# power_board.net
KiCad netlist of a schematic drawn in EAGLE
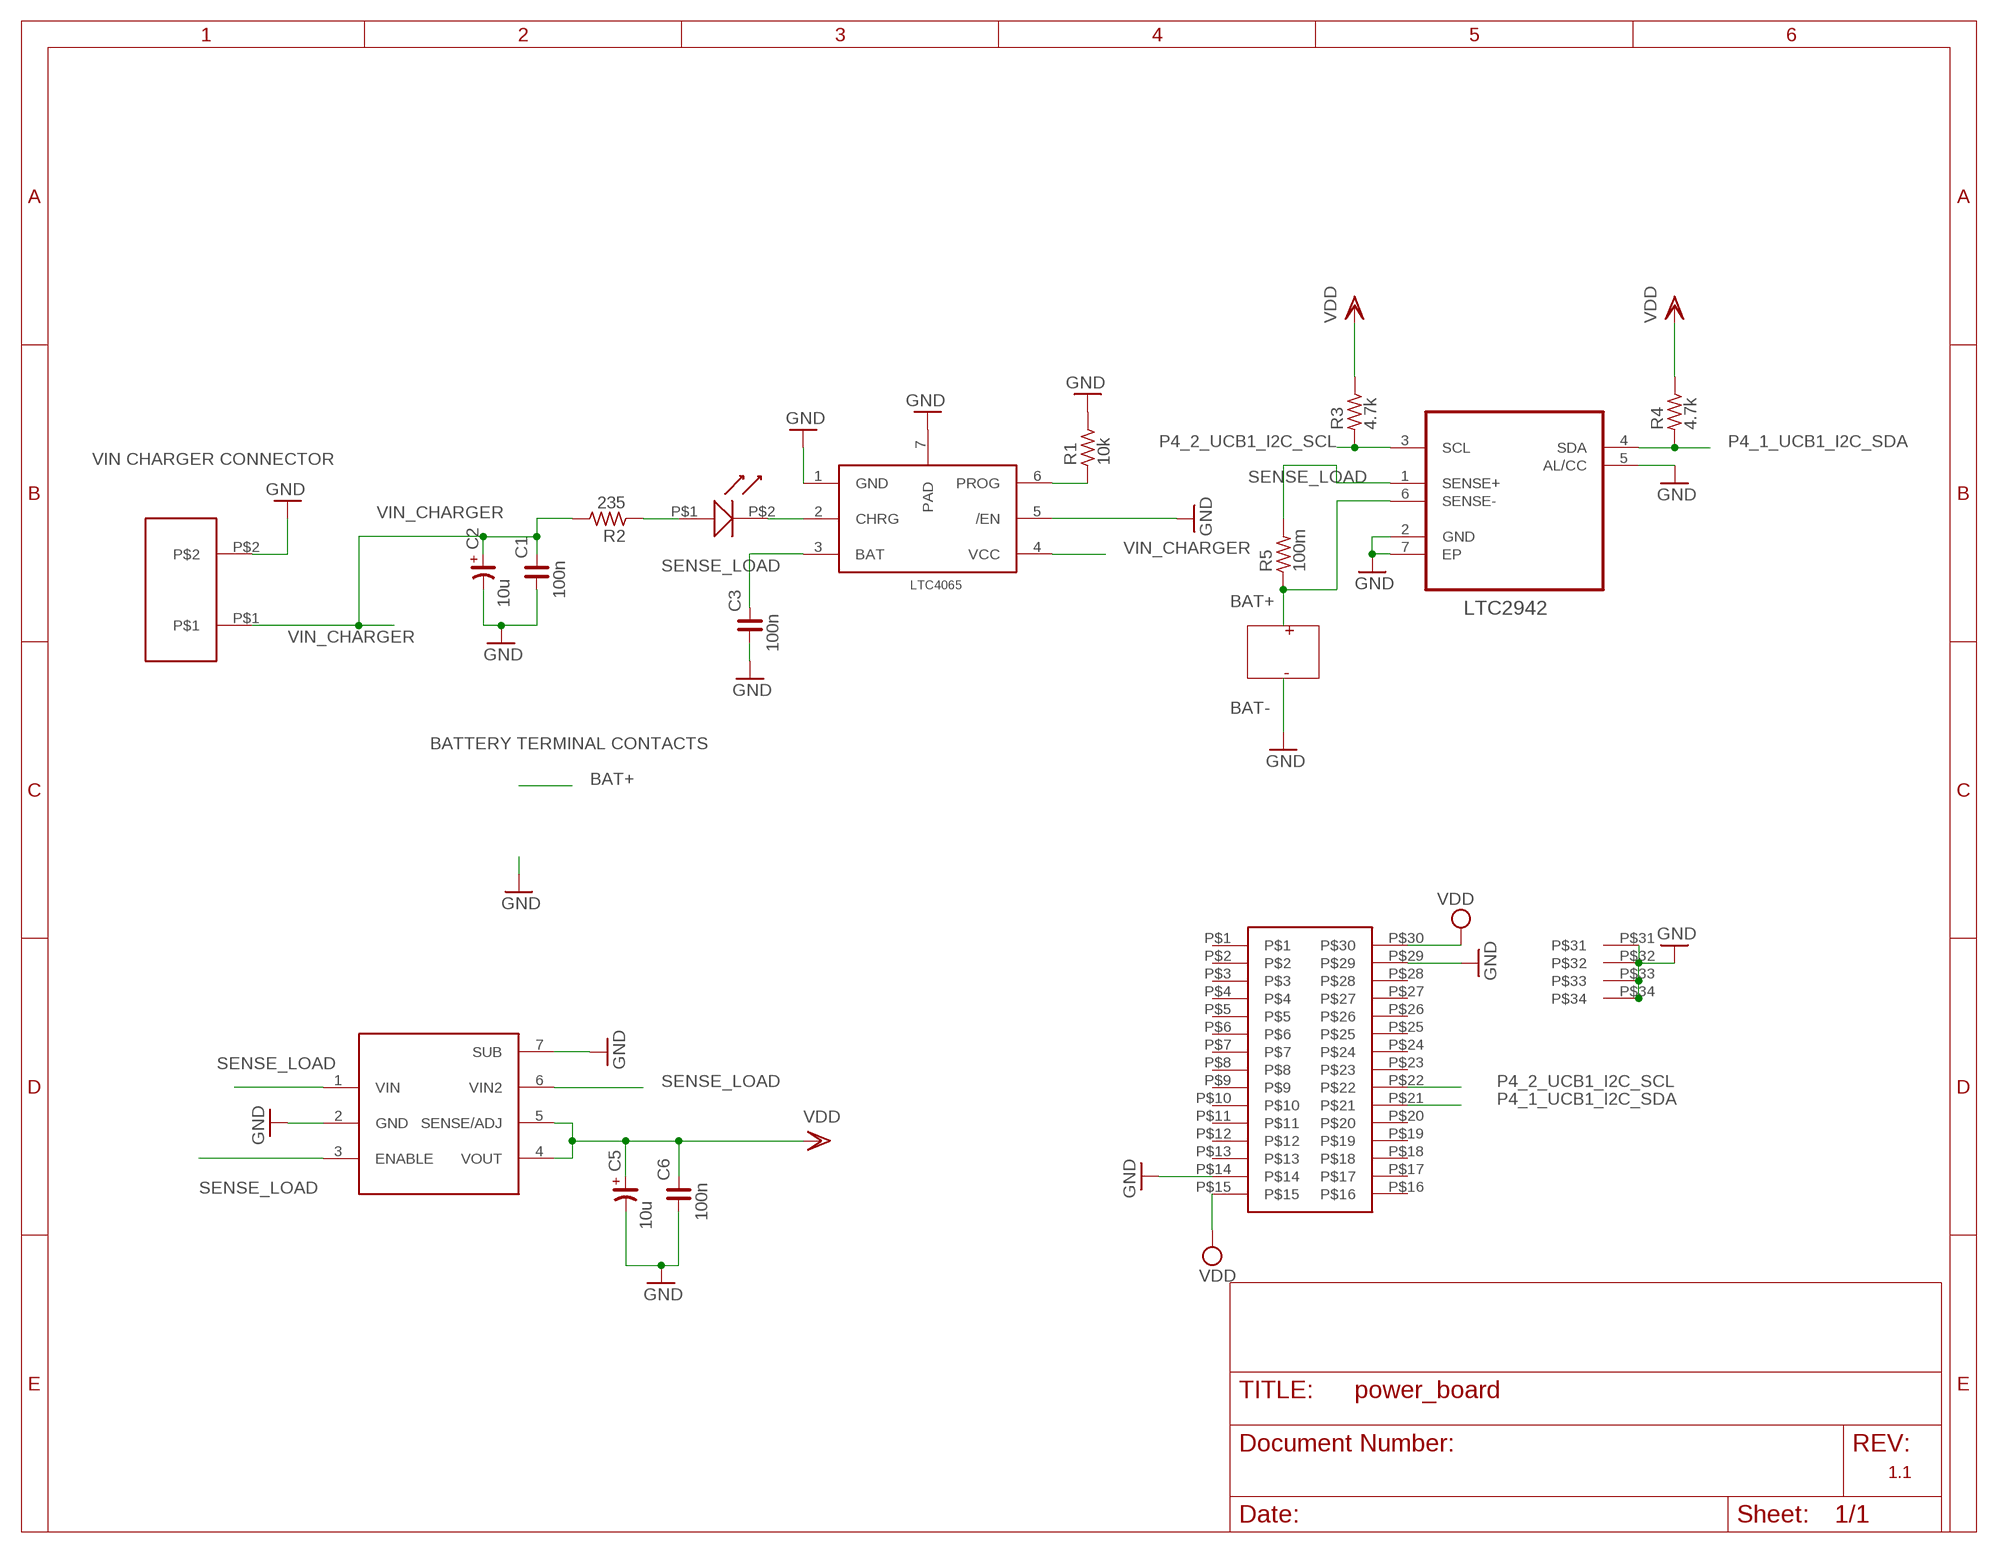
[diagram p0: schematic, sheet 1]

(export (version "E")
  (design (tool "Eeschema 10.0.6"))
  (components
    (comp (ref "C1")
      (value "100n")
      (footprint "eagle-import:C0402")
      (libsource (lib "eagle-import") (part "C_0402"))
    )
    (comp (ref "C2")
      (value "10u")
      (footprint "eagle-import:C0402")
      (libsource (lib "eagle-import") (part "CP_"))
    )
    (comp (ref "C3")
      (value "100n")
      (footprint "eagle-import:C0402")
      (libsource (lib "eagle-import") (part "C_0402"))
    )
    (comp (ref "C5")
      (value "10u")
      (footprint "eagle-import:C0402")
      (libsource (lib "eagle-import") (part "CP_"))
    )
    (comp (ref "C6")
      (value "100n")
      (footprint "eagle-import:C0402")
      (libsource (lib "eagle-import") (part "C_0402"))
    )
    (comp (ref "R1")
      (value "10k")
      (footprint "eagle-import:R0402")
      (libsource (lib "eagle-import") (part "R_0402"))
    )
    (comp (ref "R2")
      (value "235")
      (footprint "eagle-import:R0402")
      (libsource (lib "eagle-import") (part "R_0402"))
    )
    (comp (ref "R3")
      (value "4.7k")
      (footprint "eagle-import:R0402")
      (libsource (lib "eagle-import") (part "R_0402"))
    )
    (comp (ref "R4")
      (value "4.7k")
      (footprint "eagle-import:R0402")
      (libsource (lib "eagle-import") (part "R_0402"))
    )
    (comp (ref "R5")
      (value "100m")
      (footprint "eagle-import:R0402")
      (libsource (lib "eagle-import") (part "R_0402"))
    )
    (comp (ref "U$1")
      (value "LTC4065")
      (footprint "eagle-import:LTC4065")
      (libsource (lib "eagle-import") (part "LTC4065"))
    )
    (comp (ref "U$2")
      (value "LED0402")
      (footprint "eagle-import:LED_0402")
      (libsource (lib "eagle-import") (part "LED0402"))
    )
    (comp (ref "U$3")
      (value "55909-0374_PLUG")
      (footprint "eagle-import:55909-0374_PLUG")
      (libsource (lib "eagle-import") (part "55909-0374_PLUG"))
    )
    (comp (ref "U$4")
      (value "NCP606")
      (footprint "eagle-import:NCP606")
      (libsource (lib "eagle-import") (part "NCP606"))
    )
    (comp (ref "U$5")
      (value "ASR_2_REC")
      (footprint "eagle-import:ASR_2_CONN")
      (libsource (lib "eagle-import") (part "ASR_2_REC"))
    )
    (comp (ref "U1")
      (value "LTC2942CDCBTRMPBF")
      (footprint "eagle-import:DFN200X300X80-7N")
      (fields (field (name "MPN") "LTC2942CDCB#TRMPBF"))
      (libsource (lib "eagle-import") (part "LTC2942CDCBTRMPBF"))
    )
  )
  (nets
    (net (code "1") (name "/BAT+") (class "Default")
      (node (ref "R5") (pin "1") (pinfunction "1_1") (pintype "passive"))
      (node (ref "U1") (pin "6") (pinfunction "SENSE-_6") (pintype "input"))
    )
    (net (code "2") (name "/P4_1_UCB1_I2C_SDA") (class "Default")
      (node (ref "R4") (pin "1") (pinfunction "1_1") (pintype "passive"))
      (node (ref "U$3") (pin "P$21") (pinfunction "P$21_P$21") (pintype "bidirectional"))
      (node (ref "U1") (pin "4") (pinfunction "SDA_4") (pintype "bidirectional"))
    )
    (net (code "3") (name "/P4_2_UCB1_I2C_SCL") (class "Default")
      (node (ref "R3") (pin "1") (pinfunction "1_1") (pintype "passive"))
      (node (ref "U$3") (pin "P$22") (pinfunction "P$22_P$22") (pintype "bidirectional"))
      (node (ref "U1") (pin "3") (pinfunction "SCL_3") (pintype "input"))
    )
    (net (code "4") (name "/SENSE_LOAD") (class "Default")
      (node (ref "C3") (pin "2") (pinfunction "2_2") (pintype "passive"))
      (node (ref "R5") (pin "2") (pinfunction "2_2") (pintype "passive"))
      (node (ref "U$1") (pin "3") (pinfunction "BAT_3") (pintype "bidirectional"))
      (node (ref "U$4") (pin "1") (pinfunction "VIN_1") (pintype "bidirectional"))
      (node (ref "U$4") (pin "3") (pinfunction "ENABLE_3") (pintype "bidirectional"))
      (node (ref "U$4") (pin "6") (pinfunction "VIN2_6") (pintype "bidirectional"))
      (node (ref "U1") (pin "1") (pinfunction "SENSE+_1") (pintype "input"))
    )
    (net (code "5") (name "/VIN_CHARGER") (class "Default")
      (node (ref "C1") (pin "2") (pinfunction "2_2") (pintype "passive"))
      (node (ref "C2") (pin "1") (pinfunction "+_1") (pintype "passive"))
      (node (ref "R2") (pin "2") (pinfunction "2_2") (pintype "passive"))
      (node (ref "U$1") (pin "4") (pinfunction "VCC_4") (pintype "bidirectional"))
      (node (ref "U$5") (pin "P$1") (pinfunction "P$1_P$1") (pintype "bidirectional"))
    )
    (net (code "6") (name "GND") (class "Default")
      (node (ref "C1") (pin "1") (pinfunction "1_1") (pintype "passive"))
      (node (ref "C2") (pin "2") (pinfunction "-_2") (pintype "passive"))
      (node (ref "C3") (pin "1") (pinfunction "1_1") (pintype "passive"))
      (node (ref "C5") (pin "2") (pinfunction "-_2") (pintype "passive"))
      (node (ref "C6") (pin "1") (pinfunction "1_1") (pintype "passive"))
      (node (ref "R1") (pin "2") (pinfunction "2_2") (pintype "passive"))
      (node (ref "U$1") (pin "1") (pinfunction "GND_1") (pintype "bidirectional"))
      (node (ref "U$1") (pin "5") (pinfunction "/EN_5") (pintype "bidirectional"))
      (node (ref "U$1") (pin "7") (pinfunction "PAD_7") (pintype "bidirectional"))
      (node (ref "U$3") (pin "P$14") (pinfunction "P$14_P$14") (pintype "bidirectional"))
      (node (ref "U$3") (pin "P$29") (pinfunction "P$29_P$29") (pintype "bidirectional"))
      (node (ref "U$3") (pin "P$31") (pinfunction "P$31_P$31") (pintype "bidirectional"))
      (node (ref "U$3") (pin "P$32") (pinfunction "P$32_P$32") (pintype "bidirectional"))
      (node (ref "U$3") (pin "P$33") (pinfunction "P$33_P$33") (pintype "bidirectional"))
      (node (ref "U$3") (pin "P$34") (pinfunction "P$34_P$34") (pintype "bidirectional"))
      (node (ref "U$4") (pin "2") (pinfunction "GND_2") (pintype "bidirectional"))
      (node (ref "U$4") (pin "7") (pinfunction "SUB_7") (pintype "bidirectional"))
      (node (ref "U$5") (pin "P$2") (pinfunction "P$2_P$2") (pintype "bidirectional"))
      (node (ref "U1") (pin "2") (pinfunction "GND_2") (pintype "passive"))
      (node (ref "U1") (pin "5") (pinfunction "AL/CC_5") (pintype "bidirectional"))
      (node (ref "U1") (pin "7") (pinfunction "EP_7") (pintype "passive"))
    )
    (net (code "7") (name "Net-(U$1-CHRG)") (class "Default")
      (node (ref "U$1") (pin "2") (pinfunction "CHRG_2") (pintype "bidirectional"))
      (node (ref "U$2") (pin "P$2") (pinfunction "K_P$2") (pintype "bidirectional"))
    )
    (net (code "8") (name "Net-(U$1-PROG)") (class "Default")
      (node (ref "R1") (pin "1") (pinfunction "1_1") (pintype "passive"))
      (node (ref "U$1") (pin "6") (pinfunction "PROG_6") (pintype "bidirectional"))
    )
    (net (code "9") (name "Net-(U$2-A)") (class "Default")
      (node (ref "R2") (pin "1") (pinfunction "1_1") (pintype "passive"))
      (node (ref "U$2") (pin "P$1") (pinfunction "A_P$1") (pintype "bidirectional"))
    )
    (net (code "10") (name "VDD") (class "Default")
      (node (ref "C5") (pin "1") (pinfunction "+_1") (pintype "passive"))
      (node (ref "C6") (pin "2") (pinfunction "2_2") (pintype "passive"))
      (node (ref "R3") (pin "2") (pinfunction "2_2") (pintype "passive"))
      (node (ref "R4") (pin "2") (pinfunction "2_2") (pintype "passive"))
      (node (ref "U$3") (pin "P$15") (pinfunction "P$15_P$15") (pintype "bidirectional"))
      (node (ref "U$3") (pin "P$30") (pinfunction "P$30_P$30") (pintype "bidirectional"))
      (node (ref "U$4") (pin "4") (pinfunction "VOUT_4") (pintype "bidirectional"))
      (node (ref "U$4") (pin "5") (pinfunction "SENSE/ADJ_5") (pintype "bidirectional"))
    )
    (net (code "11") (name "unconnected-(U$3-PadP$1)") (class "Default")
      (node (ref "U$3") (pin "P$1") (pinfunction "P$1_P$1") (pintype "bidirectional"))
    )
    (net (code "12") (name "unconnected-(U$3-PadP$2)") (class "Default")
      (node (ref "U$3") (pin "P$2") (pinfunction "P$2_P$2") (pintype "bidirectional"))
    )
    (net (code "13") (name "unconnected-(U$3-PadP$3)") (class "Default")
      (node (ref "U$3") (pin "P$3") (pinfunction "P$3_P$3") (pintype "bidirectional"))
    )
    (net (code "14") (name "unconnected-(U$3-PadP$4)") (class "Default")
      (node (ref "U$3") (pin "P$4") (pinfunction "P$4_P$4") (pintype "bidirectional"))
    )
    (net (code "15") (name "unconnected-(U$3-PadP$5)") (class "Default")
      (node (ref "U$3") (pin "P$5") (pinfunction "P$5_P$5") (pintype "bidirectional"))
    )
    (net (code "16") (name "unconnected-(U$3-PadP$6)") (class "Default")
      (node (ref "U$3") (pin "P$6") (pinfunction "P$6_P$6") (pintype "bidirectional"))
    )
    (net (code "17") (name "unconnected-(U$3-PadP$7)") (class "Default")
      (node (ref "U$3") (pin "P$7") (pinfunction "P$7_P$7") (pintype "bidirectional"))
    )
    (net (code "18") (name "unconnected-(U$3-PadP$8)") (class "Default")
      (node (ref "U$3") (pin "P$8") (pinfunction "P$8_P$8") (pintype "bidirectional"))
    )
    (net (code "19") (name "unconnected-(U$3-PadP$9)") (class "Default")
      (node (ref "U$3") (pin "P$9") (pinfunction "P$9_P$9") (pintype "bidirectional"))
    )
    (net (code "20") (name "unconnected-(U$3-PadP$10)") (class "Default")
      (node (ref "U$3") (pin "P$10") (pinfunction "P$10_P$10") (pintype "bidirectional"))
    )
    (net (code "21") (name "unconnected-(U$3-PadP$11)") (class "Default")
      (node (ref "U$3") (pin "P$11") (pinfunction "P$11_P$11") (pintype "bidirectional"))
    )
    (net (code "22") (name "unconnected-(U$3-PadP$12)") (class "Default")
      (node (ref "U$3") (pin "P$12") (pinfunction "P$12_P$12") (pintype "bidirectional"))
    )
    (net (code "23") (name "unconnected-(U$3-PadP$13)") (class "Default")
      (node (ref "U$3") (pin "P$13") (pinfunction "P$13_P$13") (pintype "bidirectional"))
    )
    (net (code "24") (name "unconnected-(U$3-PadP$16)") (class "Default")
      (node (ref "U$3") (pin "P$16") (pinfunction "P$16_P$16") (pintype "bidirectional"))
    )
    (net (code "25") (name "unconnected-(U$3-PadP$17)") (class "Default")
      (node (ref "U$3") (pin "P$17") (pinfunction "P$17_P$17") (pintype "bidirectional"))
    )
    (net (code "26") (name "unconnected-(U$3-PadP$18)") (class "Default")
      (node (ref "U$3") (pin "P$18") (pinfunction "P$18_P$18") (pintype "bidirectional"))
    )
    (net (code "27") (name "unconnected-(U$3-PadP$19)") (class "Default")
      (node (ref "U$3") (pin "P$19") (pinfunction "P$19_P$19") (pintype "bidirectional"))
    )
    (net (code "28") (name "unconnected-(U$3-PadP$20)") (class "Default")
      (node (ref "U$3") (pin "P$20") (pinfunction "P$20_P$20") (pintype "bidirectional"))
    )
    (net (code "29") (name "unconnected-(U$3-PadP$23)") (class "Default")
      (node (ref "U$3") (pin "P$23") (pinfunction "P$23_P$23") (pintype "bidirectional"))
    )
    (net (code "30") (name "unconnected-(U$3-PadP$24)") (class "Default")
      (node (ref "U$3") (pin "P$24") (pinfunction "P$24_P$24") (pintype "bidirectional"))
    )
    (net (code "31") (name "unconnected-(U$3-PadP$25)") (class "Default")
      (node (ref "U$3") (pin "P$25") (pinfunction "P$25_P$25") (pintype "bidirectional"))
    )
    (net (code "32") (name "unconnected-(U$3-PadP$26)") (class "Default")
      (node (ref "U$3") (pin "P$26") (pinfunction "P$26_P$26") (pintype "bidirectional"))
    )
    (net (code "33") (name "unconnected-(U$3-PadP$27)") (class "Default")
      (node (ref "U$3") (pin "P$27") (pinfunction "P$27_P$27") (pintype "bidirectional"))
    )
    (net (code "34") (name "unconnected-(U$3-PadP$28)") (class "Default")
      (node (ref "U$3") (pin "P$28") (pinfunction "P$28_P$28") (pintype "bidirectional"))
    )
  )
)
